# BPMLabLineRX3_2.net
KiCad netlist of a schematic drawn in EAGLE
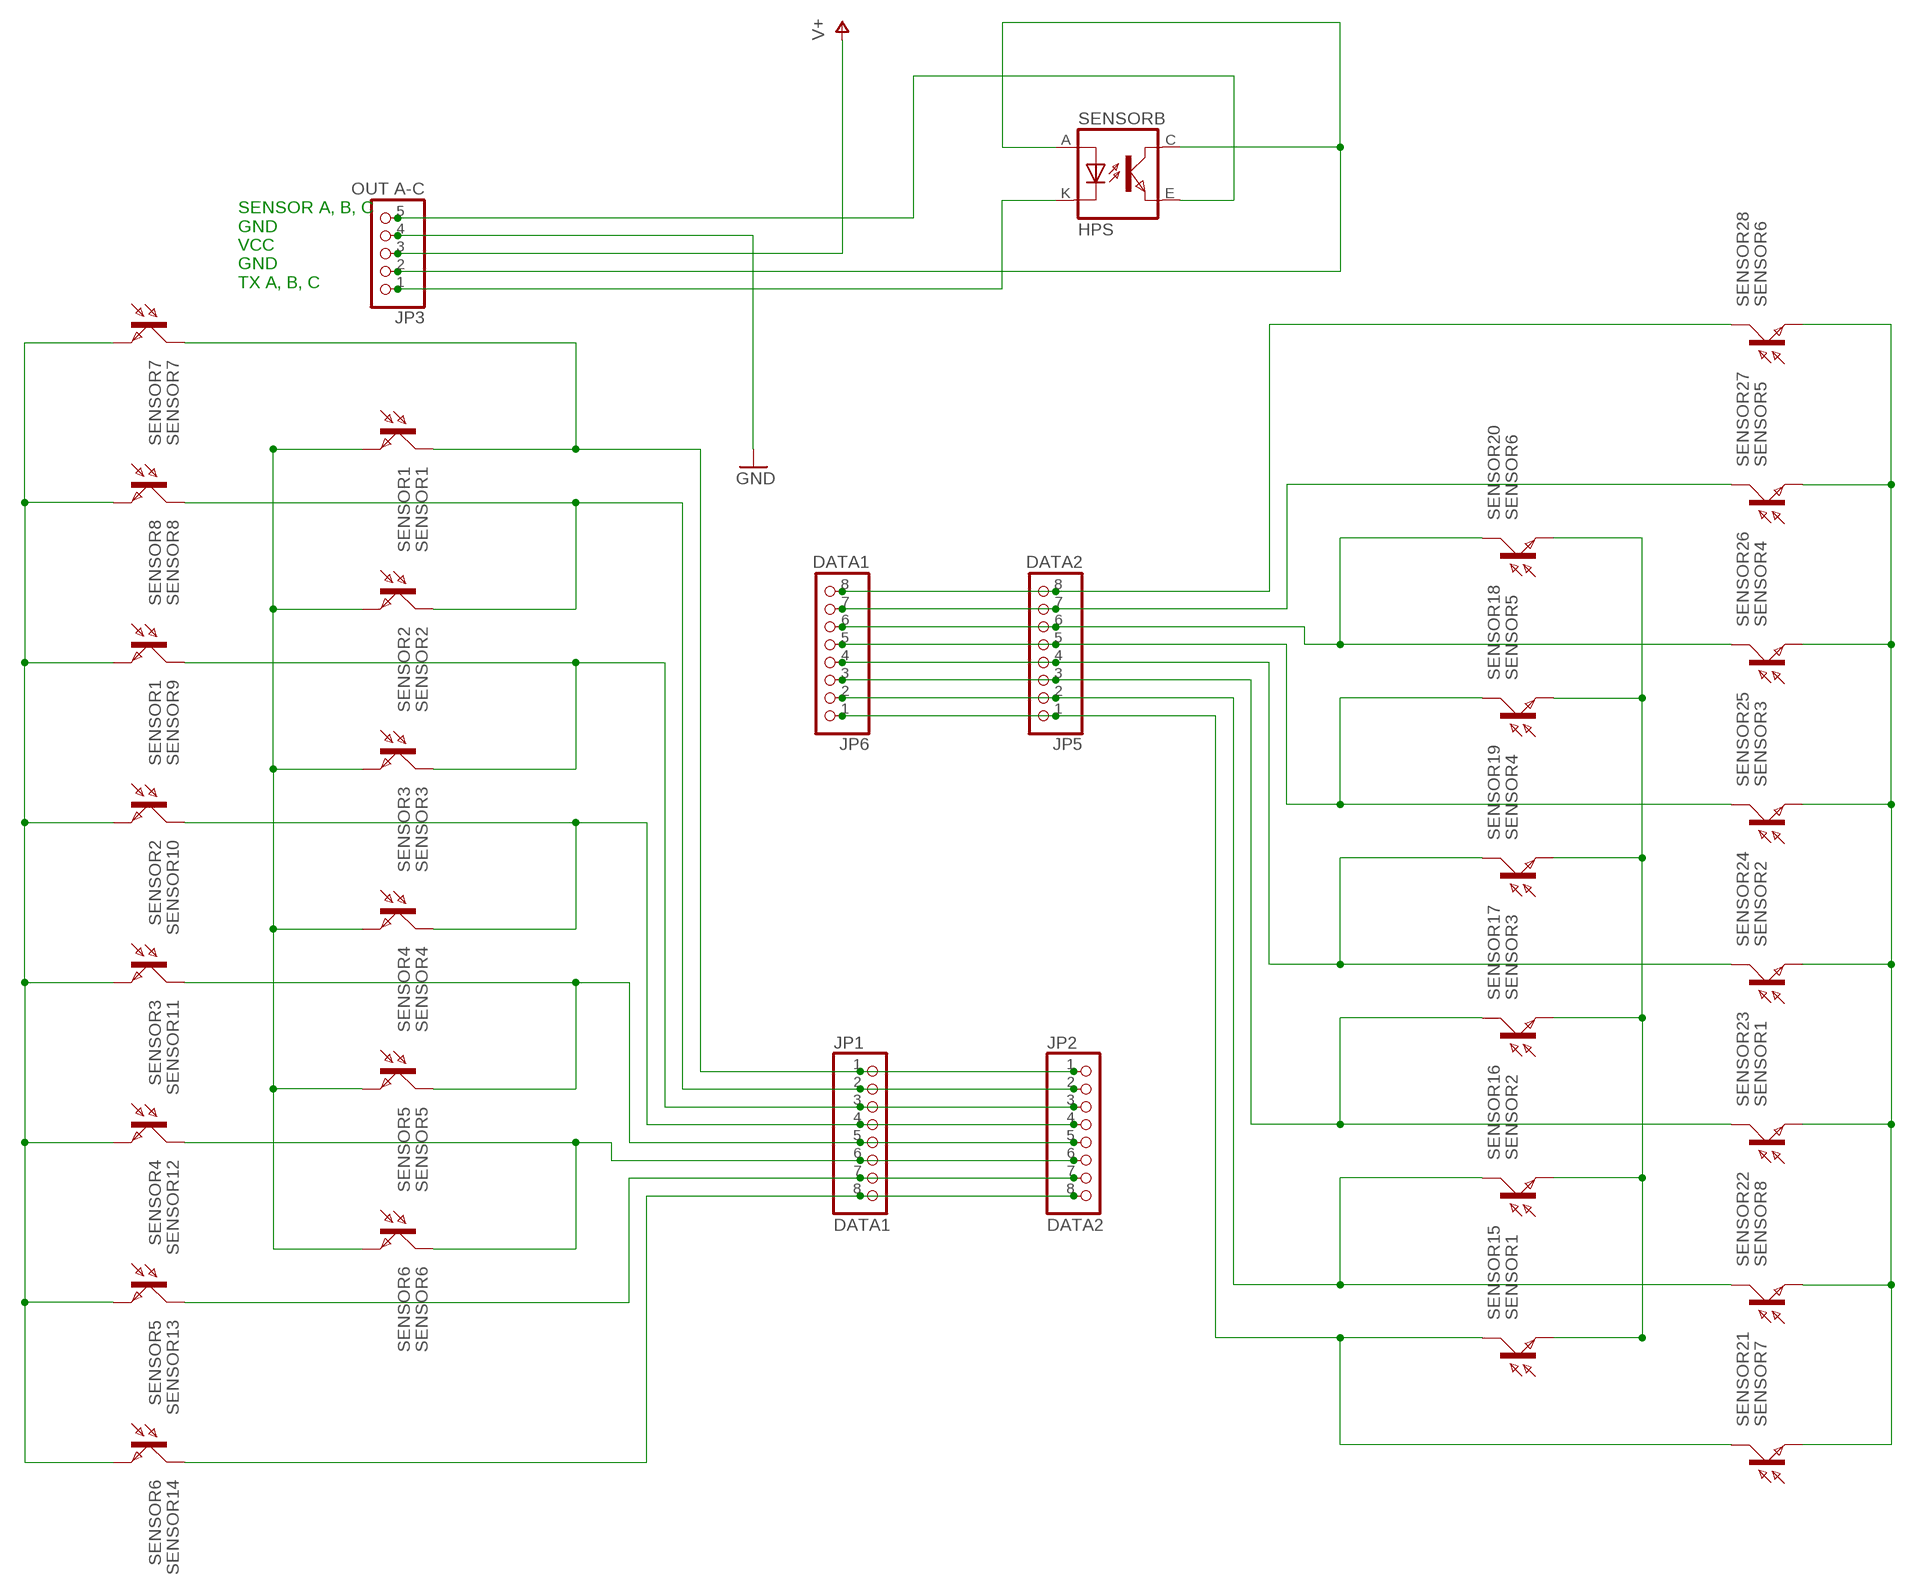
[diagram p0: schematic, sheet 1]

(export (version "E")
  (design (tool "Eeschema 10.0.6"))
  (components
    (comp (ref "JP1")
      (value "DATA1")
      (footprint "eagle-import:1X08")
      (libsource (lib "eagle-import") (part "PINHD-1X8"))
    )
    (comp (ref "JP2")
      (value "DATA2")
      (footprint "eagle-import:1X08")
      (libsource (lib "eagle-import") (part "PINHD-1X8"))
    )
    (comp (ref "JP3")
      (value "OUT A-C")
      (footprint "eagle-import:1X05")
      (libsource (lib "eagle-import") (part "PINHD-1X5"))
    )
    (comp (ref "JP5")
      (value "DATA2")
      (footprint "eagle-import:1X08")
      (libsource (lib "eagle-import") (part "PINHD-1X8"))
    )
    (comp (ref "JP6")
      (value "DATA1")
      (footprint "eagle-import:1X08")
      (libsource (lib "eagle-import") (part "PINHD-1X8"))
    )
    (comp (ref "SENSOR1")
      (value "SENSOR1")
      (footprint "eagle-import:BPX81")
      (libsource (lib "eagle-import") (part "BPX81"))
    )
    (comp (ref "SENSOR2")
      (value "SENSOR2")
      (footprint "eagle-import:BPX81")
      (libsource (lib "eagle-import") (part "BPX81"))
    )
    (comp (ref "SENSOR3")
      (value "SENSOR3")
      (footprint "eagle-import:BPX81")
      (libsource (lib "eagle-import") (part "BPX81"))
    )
    (comp (ref "SENSOR4")
      (value "SENSOR4")
      (footprint "eagle-import:BPX81")
      (libsource (lib "eagle-import") (part "BPX81"))
    )
    (comp (ref "SENSOR5")
      (value "SENSOR5")
      (footprint "eagle-import:BPX81")
      (libsource (lib "eagle-import") (part "BPX81"))
    )
    (comp (ref "SENSOR6")
      (value "SENSOR6")
      (footprint "eagle-import:BPX81")
      (libsource (lib "eagle-import") (part "BPX81"))
    )
    (comp (ref "SENSOR7")
      (value "SENSOR7")
      (footprint "eagle-import:BPX81")
      (libsource (lib "eagle-import") (part "BPX81"))
    )
    (comp (ref "SENSOR8")
      (value "SENSOR8")
      (footprint "eagle-import:BPX81")
      (libsource (lib "eagle-import") (part "BPX81"))
    )
    (comp (ref "SENSOR9")
      (value "SENSOR1")
      (footprint "eagle-import:BPX81")
      (libsource (lib "eagle-import") (part "BPX81"))
    )
    (comp (ref "SENSOR10")
      (value "SENSOR2")
      (footprint "eagle-import:BPX81")
      (libsource (lib "eagle-import") (part "BPX81"))
    )
    (comp (ref "SENSOR11")
      (value "SENSOR3")
      (footprint "eagle-import:BPX81")
      (libsource (lib "eagle-import") (part "BPX81"))
    )
    (comp (ref "SENSOR12")
      (value "SENSOR4")
      (footprint "eagle-import:BPX81")
      (libsource (lib "eagle-import") (part "BPX81"))
    )
    (comp (ref "SENSOR13")
      (value "SENSOR5")
      (footprint "eagle-import:BPX81")
      (libsource (lib "eagle-import") (part "BPX81"))
    )
    (comp (ref "SENSOR14")
      (value "SENSOR6")
      (footprint "eagle-import:BPX81")
      (libsource (lib "eagle-import") (part "BPX81"))
    )
    (comp (ref "SENSOR15")
      (value "SENSOR1")
      (footprint "eagle-import:BPX81")
      (libsource (lib "eagle-import") (part "BPX81"))
    )
    (comp (ref "SENSOR16")
      (value "SENSOR2")
      (footprint "eagle-import:BPX81")
      (libsource (lib "eagle-import") (part "BPX81"))
    )
    (comp (ref "SENSOR17")
      (value "SENSOR3")
      (footprint "eagle-import:BPX81")
      (libsource (lib "eagle-import") (part "BPX81"))
    )
    (comp (ref "SENSOR18")
      (value "SENSOR5")
      (footprint "eagle-import:BPX81")
      (libsource (lib "eagle-import") (part "BPX81"))
    )
    (comp (ref "SENSOR19")
      (value "SENSOR4")
      (footprint "eagle-import:BPX81")
      (libsource (lib "eagle-import") (part "BPX81"))
    )
    (comp (ref "SENSOR20")
      (value "SENSOR6")
      (footprint "eagle-import:BPX81")
      (libsource (lib "eagle-import") (part "BPX81"))
    )
    (comp (ref "SENSOR21")
      (value "SENSOR7")
      (footprint "eagle-import:BPX81")
      (libsource (lib "eagle-import") (part "BPX81"))
    )
    (comp (ref "SENSOR22")
      (value "SENSOR8")
      (footprint "eagle-import:BPX81")
      (libsource (lib "eagle-import") (part "BPX81"))
    )
    (comp (ref "SENSOR23")
      (value "SENSOR1")
      (footprint "eagle-import:BPX81")
      (libsource (lib "eagle-import") (part "BPX81"))
    )
    (comp (ref "SENSOR24")
      (value "SENSOR2")
      (footprint "eagle-import:BPX81")
      (libsource (lib "eagle-import") (part "BPX81"))
    )
    (comp (ref "SENSOR25")
      (value "SENSOR3")
      (footprint "eagle-import:BPX81")
      (libsource (lib "eagle-import") (part "BPX81"))
    )
    (comp (ref "SENSOR26")
      (value "SENSOR4")
      (footprint "eagle-import:BPX81")
      (libsource (lib "eagle-import") (part "BPX81"))
    )
    (comp (ref "SENSOR27")
      (value "SENSOR5")
      (footprint "eagle-import:BPX81")
      (libsource (lib "eagle-import") (part "BPX81"))
    )
    (comp (ref "SENSOR28")
      (value "SENSOR6")
      (footprint "eagle-import:BPX81")
      (libsource (lib "eagle-import") (part "BPX81"))
    )
    (comp (ref "SENSORB")
      (value "HPS")
      (footprint "eagle-import:TCRT5000")
      (libsource (lib "eagle-import") (part "TCRT5000"))
    )
  )
  (nets
    (net (code "1") (name "GND") (class "Default")
      (node (ref "JP3") (pin "4") (pinfunction "4_4") (pintype "passive"))
    )
    (net (code "2") (name "Net-(JP1-Pad1)") (class "Default")
      (node (ref "JP1") (pin "1") (pinfunction "1_1") (pintype "passive"))
      (node (ref "JP2") (pin "1") (pinfunction "1_1") (pintype "passive"))
      (node (ref "SENSOR1") (pin "C") (pinfunction "C_C") (pintype "passive"))
      (node (ref "SENSOR7") (pin "C") (pinfunction "C_C") (pintype "passive"))
    )
    (net (code "3") (name "Net-(JP1-Pad2)") (class "Default")
      (node (ref "JP1") (pin "2") (pinfunction "2_2") (pintype "passive"))
      (node (ref "JP2") (pin "2") (pinfunction "2_2") (pintype "passive"))
      (node (ref "SENSOR2") (pin "C") (pinfunction "C_C") (pintype "passive"))
      (node (ref "SENSOR8") (pin "C") (pinfunction "C_C") (pintype "passive"))
    )
    (net (code "4") (name "Net-(JP1-Pad3)") (class "Default")
      (node (ref "JP1") (pin "3") (pinfunction "3_3") (pintype "passive"))
      (node (ref "JP2") (pin "3") (pinfunction "3_3") (pintype "passive"))
      (node (ref "SENSOR3") (pin "C") (pinfunction "C_C") (pintype "passive"))
      (node (ref "SENSOR9") (pin "C") (pinfunction "C_C") (pintype "passive"))
    )
    (net (code "5") (name "Net-(JP1-Pad4)") (class "Default")
      (node (ref "JP1") (pin "4") (pinfunction "4_4") (pintype "passive"))
      (node (ref "JP2") (pin "4") (pinfunction "4_4") (pintype "passive"))
      (node (ref "SENSOR10") (pin "C") (pinfunction "C_C") (pintype "passive"))
      (node (ref "SENSOR4") (pin "C") (pinfunction "C_C") (pintype "passive"))
    )
    (net (code "6") (name "Net-(JP1-Pad5)") (class "Default")
      (node (ref "JP1") (pin "5") (pinfunction "5_5") (pintype "passive"))
      (node (ref "JP2") (pin "5") (pinfunction "5_5") (pintype "passive"))
      (node (ref "SENSOR11") (pin "C") (pinfunction "C_C") (pintype "passive"))
      (node (ref "SENSOR5") (pin "C") (pinfunction "C_C") (pintype "passive"))
    )
    (net (code "7") (name "Net-(JP1-Pad6)") (class "Default")
      (node (ref "JP1") (pin "6") (pinfunction "6_6") (pintype "passive"))
      (node (ref "JP2") (pin "6") (pinfunction "6_6") (pintype "passive"))
      (node (ref "SENSOR12") (pin "C") (pinfunction "C_C") (pintype "passive"))
      (node (ref "SENSOR6") (pin "C") (pinfunction "C_C") (pintype "passive"))
    )
    (net (code "8") (name "Net-(JP1-Pad7)") (class "Default")
      (node (ref "JP1") (pin "7") (pinfunction "7_7") (pintype "passive"))
      (node (ref "JP2") (pin "7") (pinfunction "7_7") (pintype "passive"))
      (node (ref "SENSOR13") (pin "C") (pinfunction "C_C") (pintype "passive"))
    )
    (net (code "9") (name "Net-(JP1-Pad8)") (class "Default")
      (node (ref "JP1") (pin "8") (pinfunction "8_8") (pintype "passive"))
      (node (ref "JP2") (pin "8") (pinfunction "8_8") (pintype "passive"))
      (node (ref "SENSOR14") (pin "C") (pinfunction "C_C") (pintype "passive"))
    )
    (net (code "10") (name "Net-(JP5-Pad1)") (class "Default")
      (node (ref "JP5") (pin "1") (pinfunction "1_1") (pintype "passive"))
      (node (ref "JP6") (pin "1") (pinfunction "1_1") (pintype "passive"))
      (node (ref "SENSOR15") (pin "C") (pinfunction "C_C") (pintype "passive"))
      (node (ref "SENSOR21") (pin "C") (pinfunction "C_C") (pintype "passive"))
    )
    (net (code "11") (name "Net-(JP5-Pad2)") (class "Default")
      (node (ref "JP5") (pin "2") (pinfunction "2_2") (pintype "passive"))
      (node (ref "JP6") (pin "2") (pinfunction "2_2") (pintype "passive"))
      (node (ref "SENSOR16") (pin "C") (pinfunction "C_C") (pintype "passive"))
      (node (ref "SENSOR22") (pin "C") (pinfunction "C_C") (pintype "passive"))
    )
    (net (code "12") (name "Net-(JP5-Pad3)") (class "Default")
      (node (ref "JP5") (pin "3") (pinfunction "3_3") (pintype "passive"))
      (node (ref "JP6") (pin "3") (pinfunction "3_3") (pintype "passive"))
      (node (ref "SENSOR17") (pin "C") (pinfunction "C_C") (pintype "passive"))
      (node (ref "SENSOR23") (pin "C") (pinfunction "C_C") (pintype "passive"))
    )
    (net (code "13") (name "Net-(JP5-Pad4)") (class "Default")
      (node (ref "JP5") (pin "4") (pinfunction "4_4") (pintype "passive"))
      (node (ref "JP6") (pin "4") (pinfunction "4_4") (pintype "passive"))
      (node (ref "SENSOR19") (pin "C") (pinfunction "C_C") (pintype "passive"))
      (node (ref "SENSOR24") (pin "C") (pinfunction "C_C") (pintype "passive"))
    )
    (net (code "14") (name "Net-(JP5-Pad5)") (class "Default")
      (node (ref "JP5") (pin "5") (pinfunction "5_5") (pintype "passive"))
      (node (ref "JP6") (pin "5") (pinfunction "5_5") (pintype "passive"))
      (node (ref "SENSOR18") (pin "C") (pinfunction "C_C") (pintype "passive"))
      (node (ref "SENSOR25") (pin "C") (pinfunction "C_C") (pintype "passive"))
    )
    (net (code "15") (name "Net-(JP5-Pad6)") (class "Default")
      (node (ref "JP5") (pin "6") (pinfunction "6_6") (pintype "passive"))
      (node (ref "JP6") (pin "6") (pinfunction "6_6") (pintype "passive"))
      (node (ref "SENSOR20") (pin "C") (pinfunction "C_C") (pintype "passive"))
      (node (ref "SENSOR26") (pin "C") (pinfunction "C_C") (pintype "passive"))
    )
    (net (code "16") (name "Net-(JP5-Pad7)") (class "Default")
      (node (ref "JP5") (pin "7") (pinfunction "7_7") (pintype "passive"))
      (node (ref "JP6") (pin "7") (pinfunction "7_7") (pintype "passive"))
      (node (ref "SENSOR27") (pin "C") (pinfunction "C_C") (pintype "passive"))
    )
    (net (code "17") (name "Net-(JP5-Pad8)") (class "Default")
      (node (ref "JP5") (pin "8") (pinfunction "8_8") (pintype "passive"))
      (node (ref "JP6") (pin "8") (pinfunction "8_8") (pintype "passive"))
      (node (ref "SENSOR28") (pin "C") (pinfunction "C_C") (pintype "passive"))
    )
    (net (code "18") (name "Net-(SENSOR1-PadE)") (class "Default")
      (node (ref "SENSOR1") (pin "E") (pinfunction "E_E") (pintype "passive"))
      (node (ref "SENSOR2") (pin "E") (pinfunction "E_E") (pintype "passive"))
      (node (ref "SENSOR3") (pin "E") (pinfunction "E_E") (pintype "passive"))
      (node (ref "SENSOR4") (pin "E") (pinfunction "E_E") (pintype "passive"))
      (node (ref "SENSOR5") (pin "E") (pinfunction "E_E") (pintype "passive"))
      (node (ref "SENSOR6") (pin "E") (pinfunction "E_E") (pintype "passive"))
    )
    (net (code "19") (name "Net-(SENSOR10-PadE)") (class "Default")
      (node (ref "SENSOR10") (pin "E") (pinfunction "E_E") (pintype "passive"))
      (node (ref "SENSOR11") (pin "E") (pinfunction "E_E") (pintype "passive"))
      (node (ref "SENSOR12") (pin "E") (pinfunction "E_E") (pintype "passive"))
      (node (ref "SENSOR13") (pin "E") (pinfunction "E_E") (pintype "passive"))
      (node (ref "SENSOR14") (pin "E") (pinfunction "E_E") (pintype "passive"))
      (node (ref "SENSOR7") (pin "E") (pinfunction "E_E") (pintype "passive"))
      (node (ref "SENSOR8") (pin "E") (pinfunction "E_E") (pintype "passive"))
      (node (ref "SENSOR9") (pin "E") (pinfunction "E_E") (pintype "passive"))
    )
    (net (code "20") (name "Net-(SENSOR15-PadE)") (class "Default")
      (node (ref "SENSOR15") (pin "E") (pinfunction "E_E") (pintype "passive"))
      (node (ref "SENSOR16") (pin "E") (pinfunction "E_E") (pintype "passive"))
      (node (ref "SENSOR17") (pin "E") (pinfunction "E_E") (pintype "passive"))
      (node (ref "SENSOR18") (pin "E") (pinfunction "E_E") (pintype "passive"))
      (node (ref "SENSOR19") (pin "E") (pinfunction "E_E") (pintype "passive"))
      (node (ref "SENSOR20") (pin "E") (pinfunction "E_E") (pintype "passive"))
    )
    (net (code "21") (name "Net-(SENSOR21-PadE)") (class "Default")
      (node (ref "SENSOR21") (pin "E") (pinfunction "E_E") (pintype "passive"))
      (node (ref "SENSOR22") (pin "E") (pinfunction "E_E") (pintype "passive"))
      (node (ref "SENSOR23") (pin "E") (pinfunction "E_E") (pintype "passive"))
      (node (ref "SENSOR24") (pin "E") (pinfunction "E_E") (pintype "passive"))
      (node (ref "SENSOR25") (pin "E") (pinfunction "E_E") (pintype "passive"))
      (node (ref "SENSOR26") (pin "E") (pinfunction "E_E") (pintype "passive"))
      (node (ref "SENSOR27") (pin "E") (pinfunction "E_E") (pintype "passive"))
      (node (ref "SENSOR28") (pin "E") (pinfunction "E_E") (pintype "passive"))
    )
    (net (code "22") (name "Net-(SENSORB-ANODE)") (class "Default")
      (node (ref "JP3") (pin "2") (pinfunction "2_2") (pintype "passive"))
      (node (ref "SENSORB") (pin "A") (pinfunction "ANODE_A") (pintype "passive"))
      (node (ref "SENSORB") (pin "C") (pinfunction "COLLECTOR_C") (pintype "passive"))
    )
    (net (code "23") (name "Net-(SENSORB-CATHODE)") (class "Default")
      (node (ref "JP3") (pin "1") (pinfunction "1_1") (pintype "passive"))
      (node (ref "SENSORB") (pin "K") (pinfunction "CATHODE_K") (pintype "passive"))
    )
    (net (code "24") (name "Net-(SENSORB-EMITTER)") (class "Default")
      (node (ref "JP3") (pin "5") (pinfunction "5_5") (pintype "passive"))
      (node (ref "SENSORB") (pin "E") (pinfunction "EMITTER_E") (pintype "passive"))
    )
    (net (code "25") (name "V+") (class "Default")
      (node (ref "JP3") (pin "3") (pinfunction "3_3") (pintype "passive"))
    )
  )
)
